# pH_meter.net
KiCad netlist of a schematic drawn in EAGLE
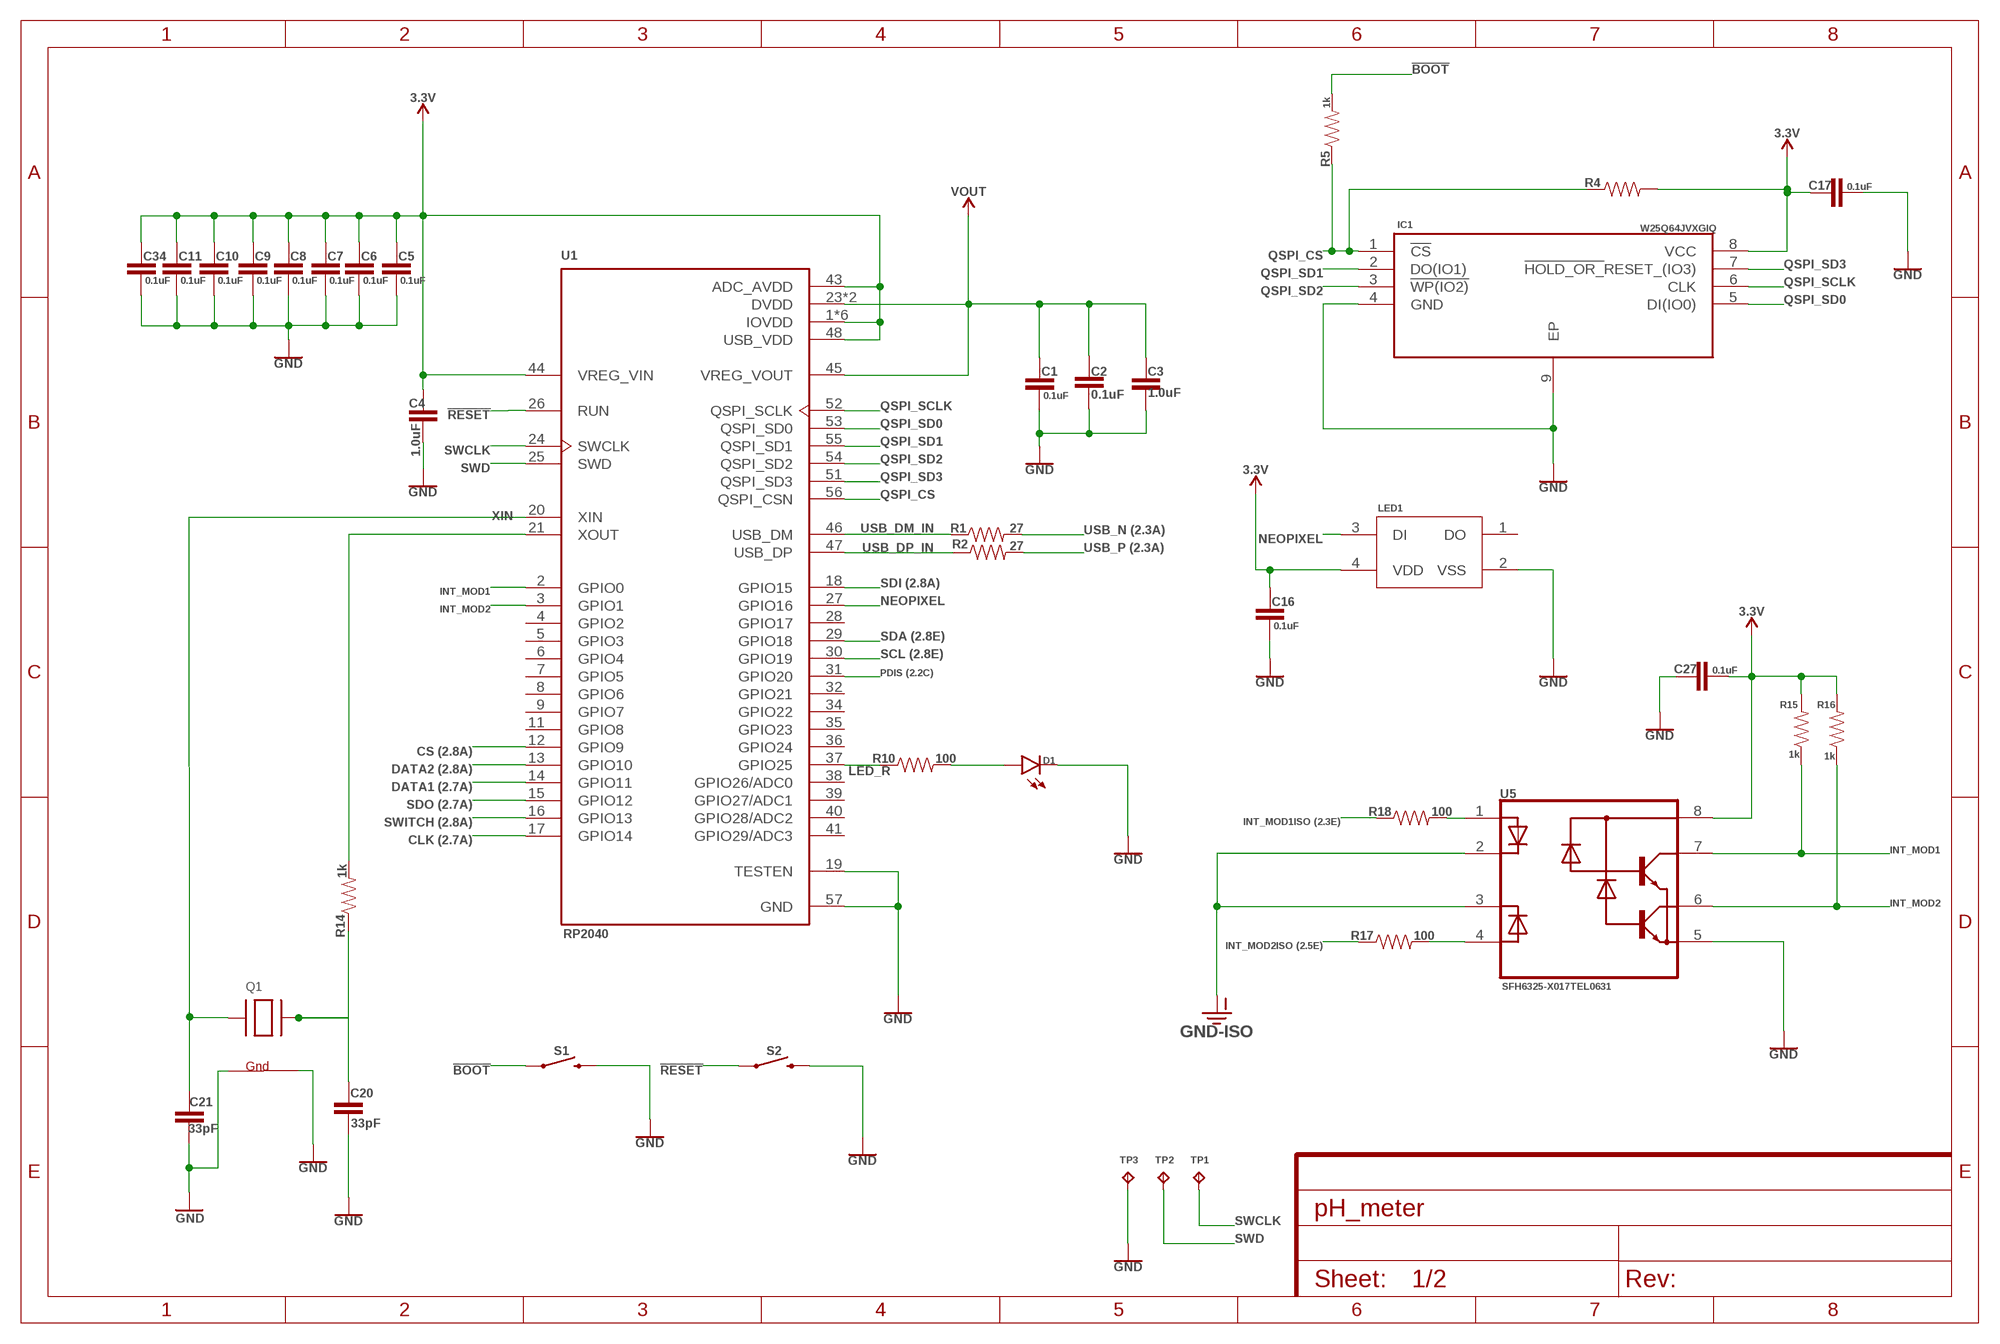
[diagram p0: schematic, sheet 1]
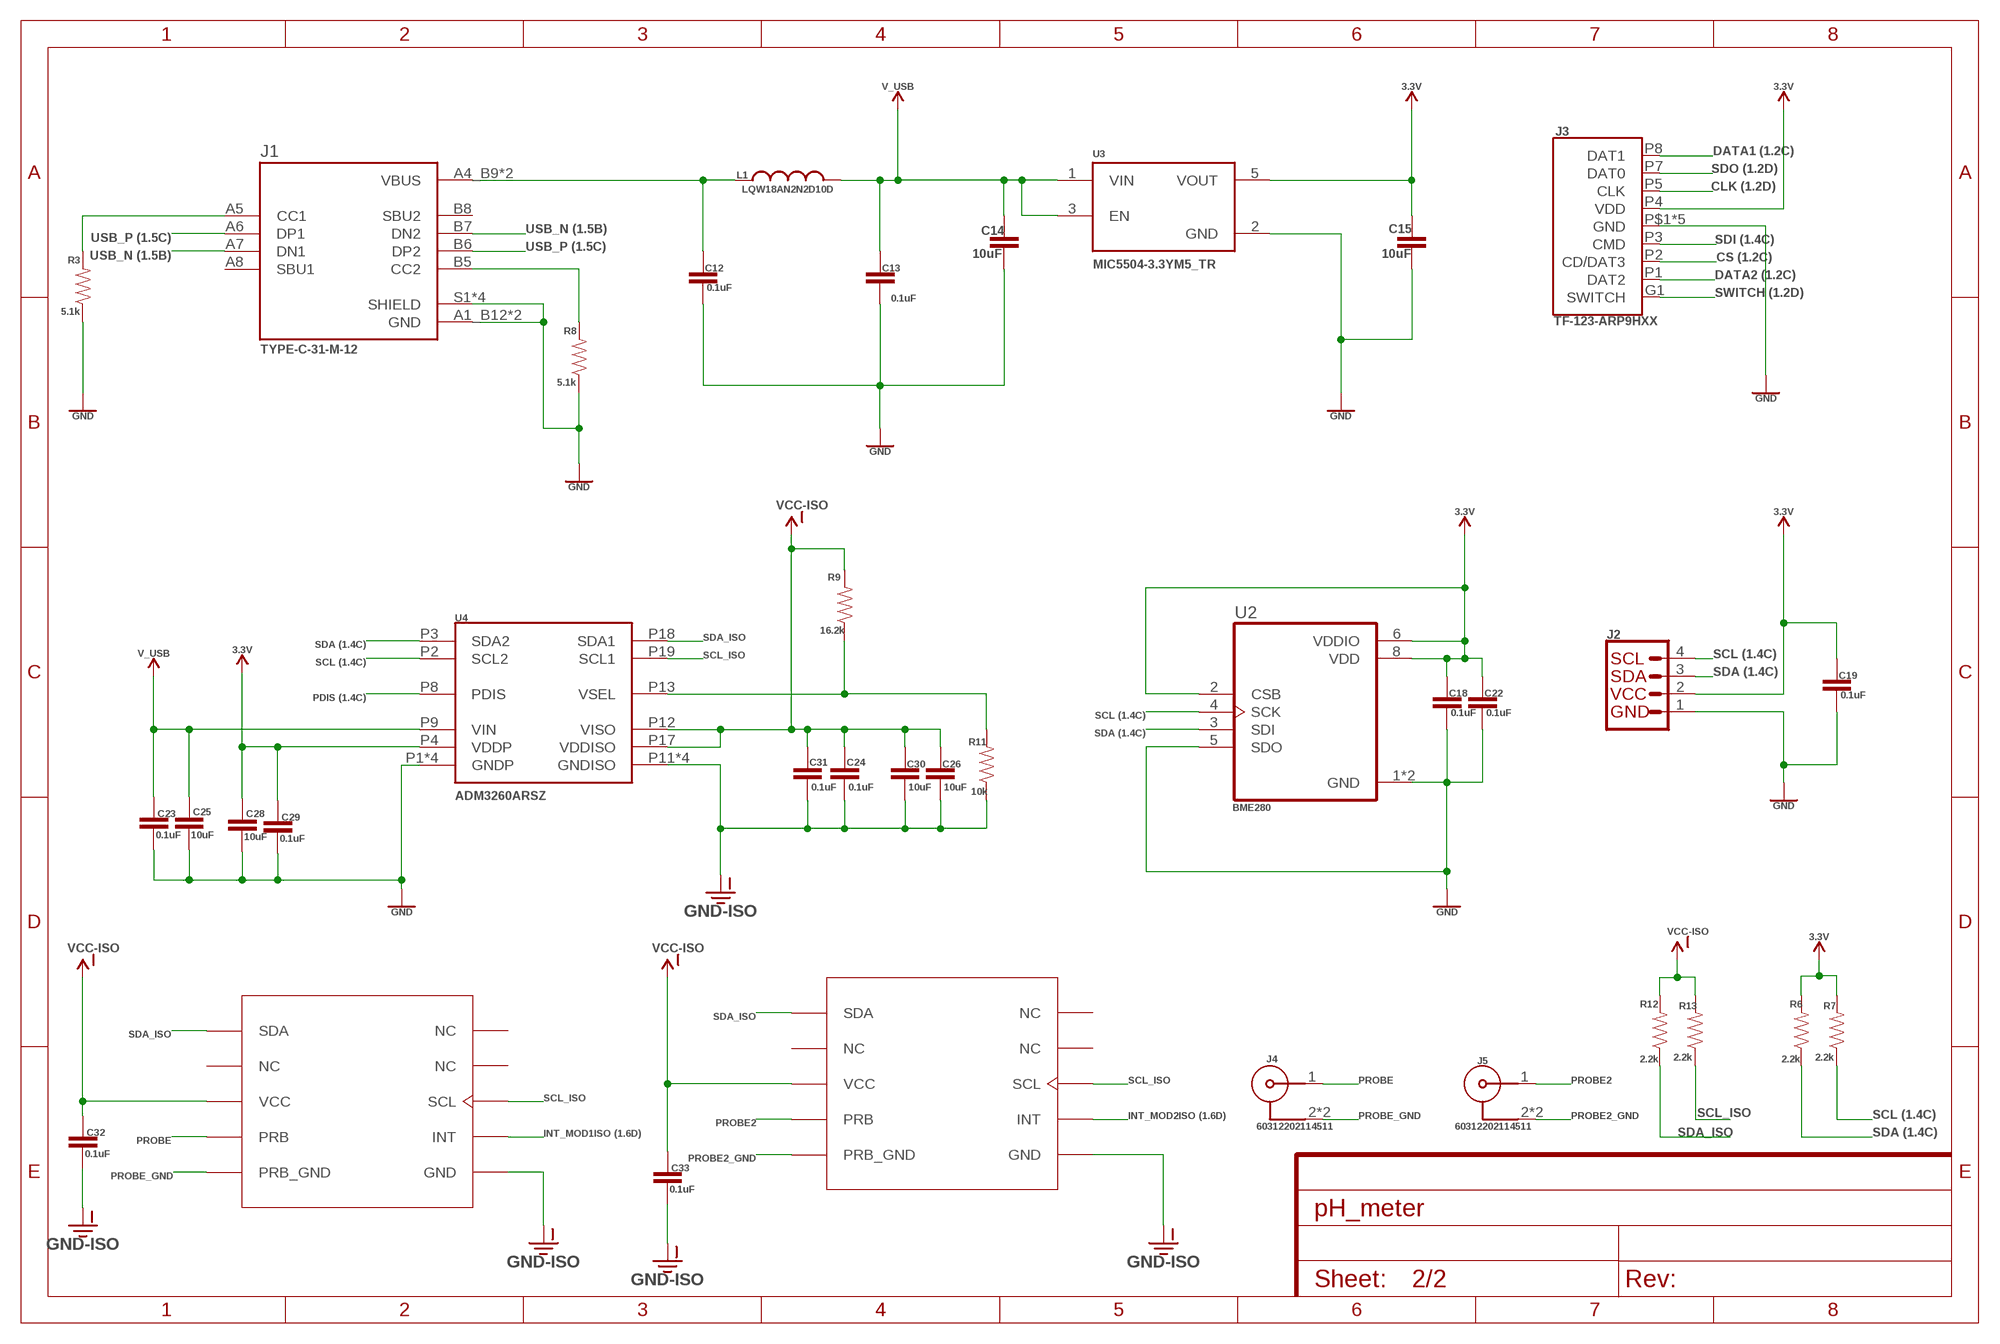
[diagram p1: schematic, sheet 2]

(export (version "E")
  (design (tool "Eeschema 10.0.6"))
  (components
    (comp (ref "C1")
      (value "0.1uF")
      (footprint "eagle-import:0603")
      (libsource (lib "eagle-import") (part "0.1UF-0603-25V-(+80/-20%)"))
    )
    (comp (ref "C2")
      (value "0.1uF")
      (footprint "eagle-import:0603")
      (libsource (lib "eagle-import") (part "0.1UF-0603-25V-(+80/-20%)"))
    )
    (comp (ref "C3")
      (value "1.0uF")
      (footprint "eagle-import:0603")
      (libsource (lib "eagle-import") (part "1.0UF-0603-16V-10%"))
    )
    (comp (ref "C4")
      (value "1.0uF")
      (footprint "eagle-import:0603")
      (libsource (lib "eagle-import") (part "1.0UF-0603-16V-10%"))
    )
    (comp (ref "C5")
      (value "0.1uF")
      (footprint "eagle-import:0603")
      (libsource (lib "eagle-import") (part "0.1UF-0603-25V-(+80/-20%)"))
    )
    (comp (ref "C6")
      (value "0.1uF")
      (footprint "eagle-import:0603")
      (libsource (lib "eagle-import") (part "0.1UF-0603-25V-(+80/-20%)"))
    )
    (comp (ref "C7")
      (value "0.1uF")
      (footprint "eagle-import:0603")
      (libsource (lib "eagle-import") (part "0.1UF-0603-25V-(+80/-20%)"))
    )
    (comp (ref "C8")
      (value "0.1uF")
      (footprint "eagle-import:0603")
      (libsource (lib "eagle-import") (part "0.1UF-0603-25V-(+80/-20%)"))
    )
    (comp (ref "C9")
      (value "0.1uF")
      (footprint "eagle-import:0603")
      (libsource (lib "eagle-import") (part "0.1UF-0603-25V-(+80/-20%)"))
    )
    (comp (ref "C10")
      (value "0.1uF")
      (footprint "eagle-import:0603")
      (libsource (lib "eagle-import") (part "0.1UF-0603-25V-(+80/-20%)"))
    )
    (comp (ref "C11")
      (value "0.1uF")
      (footprint "eagle-import:0603")
      (libsource (lib "eagle-import") (part "0.1UF-0603-25V-(+80/-20%)"))
    )
    (comp (ref "C16")
      (value "0.1uF")
      (footprint "eagle-import:0603")
      (libsource (lib "eagle-import") (part "0.1UF-0603-25V-(+80/-20%)"))
    )
    (comp (ref "C17")
      (value "0.1uF")
      (footprint "eagle-import:0603")
      (libsource (lib "eagle-import") (part "0.1UF-0603-25V-(+80/-20%)"))
    )
    (comp (ref "C20")
      (value "33pF")
      (footprint "eagle-import:0603")
      (libsource (lib "eagle-import") (part "33PF-0603-50V-5%"))
    )
    (comp (ref "C21")
      (value "33pF")
      (footprint "eagle-import:0603")
      (libsource (lib "eagle-import") (part "33PF-0603-50V-5%"))
    )
    (comp (ref "C27")
      (value "0.1uF")
      (footprint "eagle-import:0603")
      (libsource (lib "eagle-import") (part "0.1UF-0603-25V-(+80/-20%)"))
    )
    (comp (ref "C34")
      (value "0.1uF")
      (footprint "eagle-import:0603")
      (libsource (lib "eagle-import") (part "0.1UF-0603-25V-(+80/-20%)"))
    )
    (comp (ref "D1")
      (value "LED0603")
      (footprint "eagle-import:LED-0603")
      (libsource (lib "eagle-import") (part "LED0603"))
    )
    (comp (ref "IC1")
      (value "W25Q64JVXGIQ")
      (footprint "eagle-import:SON80P400X400X50-9N")
      (libsource (lib "eagle-import") (part "W25Q64JVXGIQ"))
    )
    (comp (ref "LED1")
      (value "WS2812B-2020")
      (footprint "eagle-import:WS2812B-2020")
      (fields (field (name "MF") "WorldSemi"))
      (libsource (lib "eagle-import") (part "WS2812B-2020"))
    )
    (comp (ref "Q1")
      (value "XTAL-4-3225")
      (footprint "eagle-import:NX3225")
      (libsource (lib "eagle-import") (part "XTAL-4-3225"))
    )
    (comp (ref "R1")
      (value "27")
      (footprint "eagle-import:0603")
      (libsource (lib "eagle-import") (part "27OHM-0603-1/10W-1%"))
    )
    (comp (ref "R2")
      (value "27")
      (footprint "eagle-import:0603")
      (libsource (lib "eagle-import") (part "27OHM-0603-1/10W-1%"))
    )
    (comp (ref "R4")
      (value "RESISTOR0603")
      (footprint "eagle-import:0603")
      (libsource (lib "eagle-import") (part "RESISTOR0603"))
    )
    (comp (ref "R5")
      (value "1k")
      (footprint "eagle-import:0603")
      (libsource (lib "eagle-import") (part "1KOHM-0603-1/10W-1%"))
    )
    (comp (ref "R10")
      (value "100")
      (footprint "eagle-import:0603")
      (libsource (lib "eagle-import") (part "100OHM-0603-1/10W-1%"))
    )
    (comp (ref "R14")
      (value "1k")
      (footprint "eagle-import:0603")
      (libsource (lib "eagle-import") (part "1KOHM-0603-1/10W-1%"))
    )
    (comp (ref "R15")
      (value "1k")
      (footprint "eagle-import:0603")
      (libsource (lib "eagle-import") (part "1KOHM-0603-1/10W-1%"))
    )
    (comp (ref "R16")
      (value "1k")
      (footprint "eagle-import:0603")
      (libsource (lib "eagle-import") (part "1KOHM-0603-1/10W-1%"))
    )
    (comp (ref "R17")
      (value "100")
      (footprint "eagle-import:0603")
      (libsource (lib "eagle-import") (part "100OHM-0603-1/10W-1%"))
    )
    (comp (ref "R18")
      (value "100")
      (footprint "eagle-import:0603")
      (libsource (lib "eagle-import") (part "100OHM-0603-1/10W-1%"))
    )
    (comp (ref "S1")
      (value "MOMENTARY-SWITCH-SPST-SMD-4.6X2.8MM")
      (footprint "eagle-import:TACTILE_SWITCH_SMD_4.6X2.8MM")
      (libsource (lib "eagle-import") (part "MOMENTARY-SWITCH-SPST-SMD-4.6X2.8MM"))
    )
    (comp (ref "S2")
      (value "MOMENTARY-SWITCH-SPST-SMD-4.6X2.8MM")
      (footprint "eagle-import:TACTILE_SWITCH_SMD_4.6X2.8MM")
      (libsource (lib "eagle-import") (part "MOMENTARY-SWITCH-SPST-SMD-4.6X2.8MM"))
    )
    (comp (ref "TP1")
      (value "TPB2,54")
      (footprint "eagle-import:B2,54")
      (libsource (lib "eagle-import") (part "TPB2,54"))
    )
    (comp (ref "TP2")
      (value "TPB2,54")
      (footprint "eagle-import:B2,54")
      (libsource (lib "eagle-import") (part "TPB2,54"))
    )
    (comp (ref "TP3")
      (value "TPB2,54")
      (footprint "eagle-import:B2,54")
      (libsource (lib "eagle-import") (part "TPB2,54"))
    )
    (comp (ref "U1")
      (value "RP2040")
      (footprint "eagle-import:QFN40P700X700X90-57N")
      (fields (field (name "MF") "Raspberry Pi"))
      (libsource (lib "eagle-import") (part "RP2040"))
    )
    (comp (ref "U5")
      (value "SFH6325-X017TEL0631")
      (footprint "eagle-import:SOIC127P599X175-8N")
      (libsource (lib "eagle-import") (part "SFH6325-X017TEL0631"))
    )
    (comp (ref "C12")
      (value "0.1uF")
      (footprint "eagle-import:0603")
      (libsource (lib "eagle-import") (part "0.1UF-0603-25V-(+80/-20%)"))
    )
    (comp (ref "C13")
      (value "0.1uF")
      (footprint "eagle-import:0603")
      (libsource (lib "eagle-import") (part "0.1UF-0603-25V-(+80/-20%)"))
    )
    (comp (ref "C14")
      (value "10uF")
      (footprint "eagle-import:0603")
      (libsource (lib "eagle-import") (part "10UF-0603-6.3V-20%"))
    )
    (comp (ref "C15")
      (value "10uF")
      (footprint "eagle-import:0603")
      (libsource (lib "eagle-import") (part "10UF-0603-6.3V-20%"))
    )
    (comp (ref "C18")
      (value "0.1uF")
      (footprint "eagle-import:0603")
      (libsource (lib "eagle-import") (part "0.1UF-0603-25V-5%"))
    )
    (comp (ref "C19")
      (value "0.1uF")
      (footprint "eagle-import:0603")
      (libsource (lib "eagle-import") (part "0.1UF-0603-25V-5%"))
    )
    (comp (ref "C22")
      (value "0.1uF")
      (footprint "eagle-import:0603")
      (libsource (lib "eagle-import") (part "0.1UF-0603-25V-5%"))
    )
    (comp (ref "C23")
      (value "0.1uF")
      (footprint "eagle-import:0603")
      (libsource (lib "eagle-import") (part "0.1UF-0603-25V-5%"))
    )
    (comp (ref "C24")
      (value "0.1uF")
      (footprint "eagle-import:0603")
      (libsource (lib "eagle-import") (part "0.1UF-0603-50V-10%-X7R-WE"))
    )
    (comp (ref "C25")
      (value "10uF")
      (footprint "eagle-import:0603")
      (libsource (lib "eagle-import") (part "10UF-0603-6.3V-20%"))
    )
    (comp (ref "C26")
      (value "10uF")
      (footprint "eagle-import:0603")
      (libsource (lib "eagle-import") (part "10UF-0603-6.3V-20%"))
    )
    (comp (ref "C28")
      (value "10uF")
      (footprint "eagle-import:0603")
      (libsource (lib "eagle-import") (part "10UF-0603-6.3V-20%"))
    )
    (comp (ref "C29")
      (value "0.1uF")
      (footprint "eagle-import:0603")
      (libsource (lib "eagle-import") (part "0.1UF-0603-25V-5%"))
    )
    (comp (ref "C30")
      (value "10uF")
      (footprint "eagle-import:0603")
      (libsource (lib "eagle-import") (part "10UF-0603-6.3V-20%"))
    )
    (comp (ref "C31")
      (value "0.1uF")
      (footprint "eagle-import:0603")
      (libsource (lib "eagle-import") (part "0.1UF-0603-50V-10%-X7R-WE"))
    )
    (comp (ref "C32")
      (value "0.1uF")
      (footprint "eagle-import:0603")
      (libsource (lib "eagle-import") (part "0.1UF-0603-25V-5%"))
    )
    (comp (ref "C33")
      (value "0.1uF")
      (footprint "eagle-import:0603")
      (libsource (lib "eagle-import") (part "0.1UF-0603-25V-5%"))
    )
    (comp (ref "J1")
      (value "TYPE-C-31-M-12")
      (footprint "eagle-import:HRO_TYPE-C-31-M-12")
      (fields (field (name "MF") "HRO Electronics Co., Ltd."))
      (libsource (lib "eagle-import") (part "TYPE-C-31-M-12"))
    )
    (comp (ref "J2")
      (value "QWIIC_CONNECTORJS-1MM")
      (footprint "eagle-import:1X04_1MM_RA")
      (libsource (lib "eagle-import") (part "QWIIC_CONNECTORJS-1MM"))
    )
    (comp (ref "J3")
      (value "TF-123-ARP9HXX")
      (footprint "eagle-import:MICROSDCARD")
      (libsource (lib "eagle-import") (part "TF-123-ARP9HXX"))
    )
    (comp (ref "J4")
      (value "60312202114511")
      (footprint "eagle-import:60312202114511")
      (fields (field (name "MF") "Wurth Electronics"))
      (libsource (lib "eagle-import") (part "60312202114511"))
    )
    (comp (ref "J5")
      (value "60312202114511")
      (footprint "eagle-import:60312202114511")
      (fields (field (name "MF") "Wurth Electronics"))
      (libsource (lib "eagle-import") (part "60312202114511"))
    )
    (comp (ref "L1")
      (value "LQW18AN2N2D10D")
      (footprint "eagle-import:INDC1608X100N")
      (fields (field (name "MF") "Murata"))
      (libsource (lib "eagle-import") (part "LQW18AN2N2D10D"))
    )
    (comp (ref "R3")
      (value "5.1k")
      (footprint "eagle-import:0603")
      (libsource (lib "eagle-import") (part "5.1KOHM5.1KOHM-0603-1/10W-1%"))
    )
    (comp (ref "R6")
      (value "2.2k")
      (footprint "eagle-import:0603")
      (libsource (lib "eagle-import") (part "2.2KOHM-0603-1/10W-1%"))
    )
    (comp (ref "R7")
      (value "2.2k")
      (footprint "eagle-import:0603")
      (libsource (lib "eagle-import") (part "2.2KOHM-0603-1/10W-1%"))
    )
    (comp (ref "R8")
      (value "5.1k")
      (footprint "eagle-import:0603")
      (libsource (lib "eagle-import") (part "5.1KOHM5.1KOHM-0603-1/10W-1%"))
    )
    (comp (ref "R9")
      (value "16.2k")
      (footprint "eagle-import:0603")
      (libsource (lib "eagle-import") (part "16.2KOHM-0603-1/10W-1%"))
    )
    (comp (ref "R11")
      (value "10k")
      (footprint "eagle-import:0603")
      (libsource (lib "eagle-import") (part "10KOHM-0603-1/10W-1%"))
    )
    (comp (ref "R12")
      (value "2.2k")
      (footprint "eagle-import:0603")
      (libsource (lib "eagle-import") (part "2.2KOHM-0603-1/10W-1%"))
    )
    (comp (ref "R13")
      (value "2.2k")
      (footprint "eagle-import:0603")
      (libsource (lib "eagle-import") (part "2.2KOHM-0603-1/10W-1%"))
    )
    (comp (ref "U$1")
      (value "PH-OEM")
      (footprint "eagle-import:PH_SENSOR")
      (libsource (lib "eagle-import") (part "PH-OEM"))
    )
    (comp (ref "U$2")
      (value "PH-OEM")
      (footprint "eagle-import:PH_SENSOR")
      (libsource (lib "eagle-import") (part "PH-OEM"))
    )
    (comp (ref "U2")
      (value "BME280")
      (footprint "eagle-import:PSON65P250X250X100-8N")
      (fields (field (name "MF") "Bosch"))
      (libsource (lib "eagle-import") (part "BME280"))
    )
    (comp (ref "U3")
      (value "MIC5504-3.3YM5_TR")
      (footprint "eagle-import:SOT95P280X145-5N")
      (fields (field (name "MF") "Microchip") (field (name "MP") "MIC5504-3.3YM5 TR"))
      (libsource (lib "eagle-import") (part "MIC5504-3.3YM5_TR"))
    )
    (comp (ref "U4")
      (value "ADM3260ARSZ")
      (footprint "eagle-import:SSOP20")
      (fields (field (name "MF") "Analog Devices"))
      (libsource (lib "eagle-import") (part "ADM3260ARSZ"))
    )
  )
  (nets
    (net (code "1") (name "3.3V") (class "Default")
      (node (ref "C10") (pin "1") (pinfunction "1_1") (pintype "passive"))
      (node (ref "C11") (pin "1") (pinfunction "1_1") (pintype "passive"))
      (node (ref "C15") (pin "2") (pinfunction "2_2") (pintype "passive"))
      (node (ref "C16") (pin "1") (pinfunction "1_1") (pintype "passive"))
      (node (ref "C17") (pin "1") (pinfunction "1_1") (pintype "passive"))
      (node (ref "C18") (pin "1") (pinfunction "1_1") (pintype "passive"))
      (node (ref "C19") (pin "1") (pinfunction "1_1") (pintype "passive"))
      (node (ref "C22") (pin "1") (pinfunction "1_1") (pintype "passive"))
      (node (ref "C27") (pin "2") (pinfunction "2_2") (pintype "passive"))
      (node (ref "C28") (pin "1") (pinfunction "1_1") (pintype "passive"))
      (node (ref "C29") (pin "1") (pinfunction "1_1") (pintype "passive"))
      (node (ref "C34") (pin "1") (pinfunction "1_1") (pintype "passive"))
      (node (ref "C4") (pin "1") (pinfunction "1_1") (pintype "passive"))
      (node (ref "C5") (pin "1") (pinfunction "1_1") (pintype "passive"))
      (node (ref "C6") (pin "1") (pinfunction "1_1") (pintype "passive"))
      (node (ref "C7") (pin "1") (pinfunction "1_1") (pintype "passive"))
      (node (ref "C8") (pin "1") (pinfunction "1_1") (pintype "passive"))
      (node (ref "C9") (pin "1") (pinfunction "1_1") (pintype "passive"))
      (node (ref "IC1") (pin "8") (pinfunction "VCC_8") (pintype "bidirectional"))
      (node (ref "J2") (pin "2") (pinfunction "2_2") (pintype "power_in"))
      (node (ref "J3") (pin "P4") (pinfunction "VDD_P4") (pintype "power_in"))
      (node (ref "LED1") (pin "4") (pinfunction "VDD_4") (pintype "bidirectional"))
      (node (ref "R15") (pin "2") (pinfunction "2_2") (pintype "passive"))
      (node (ref "R16") (pin "2") (pinfunction "2_2") (pintype "passive"))
      (node (ref "R4") (pin "2") (pinfunction "2_2") (pintype "passive"))
      (node (ref "R6") (pin "2") (pinfunction "2_2") (pintype "passive"))
      (node (ref "R7") (pin "2") (pinfunction "2_2") (pintype "passive"))
      (node (ref "U1") (pin "1") (pinfunction "IOVDD_1") (pintype "power_in"))
      (node (ref "U1") (pin "10") (pinfunction "IOVDD_10") (pintype "power_in"))
      (node (ref "U1") (pin "22") (pinfunction "IOVDD_22") (pintype "power_in"))
      (node (ref "U1") (pin "33") (pinfunction "IOVDD_33") (pintype "power_in"))
      (node (ref "U1") (pin "42") (pinfunction "IOVDD_42") (pintype "power_in"))
      (node (ref "U1") (pin "43") (pinfunction "ADC_AVDD_43") (pintype "power_in"))
      (node (ref "U1") (pin "44") (pinfunction "VREG_VIN_44") (pintype "input"))
      (node (ref "U1") (pin "48") (pinfunction "USB_VDD_48") (pintype "power_in"))
      (node (ref "U1") (pin "49") (pinfunction "IOVDD_49") (pintype "power_in"))
      (node (ref "U2") (pin "2") (pinfunction "CSB_2") (pintype "input"))
      (node (ref "U2") (pin "6") (pinfunction "VDDIO_6") (pintype "power_in"))
      (node (ref "U2") (pin "8") (pinfunction "VDD_8") (pintype "power_in"))
      (node (ref "U3") (pin "5") (pinfunction "VOUT_5") (pintype "output"))
      (node (ref "U4") (pin "P4") (pinfunction "VDDP_P4") (pintype "bidirectional"))
      (node (ref "U5") (pin "8") (pinfunction "C(VCC)_8") (pintype "passive"))
    )
    (net (code "2") (name "CLK") (class "Default")
      (node (ref "J3") (pin "P5") (pinfunction "CLK_P5") (pintype "bidirectional"))
      (node (ref "U1") (pin "17") (pinfunction "GPIO14_17") (pintype "bidirectional"))
    )
    (net (code "3") (name "CS") (class "Default")
      (node (ref "J3") (pin "P2") (pinfunction "CD/DAT3_P2") (pintype "bidirectional"))
      (node (ref "U1") (pin "12") (pinfunction "GPIO9_12") (pintype "bidirectional"))
    )
    (net (code "4") (name "DATA1") (class "Default")
      (node (ref "J3") (pin "P8") (pinfunction "DAT1_P8") (pintype "bidirectional"))
      (node (ref "U1") (pin "14") (pinfunction "GPIO11_14") (pintype "bidirectional"))
    )
    (net (code "5") (name "DATA2") (class "Default")
      (node (ref "J3") (pin "P1") (pinfunction "DAT2_P1") (pintype "bidirectional"))
      (node (ref "U1") (pin "13") (pinfunction "GPIO10_13") (pintype "bidirectional"))
    )
    (net (code "6") (name "GND") (class "Default")
      (node (ref "C1") (pin "2") (pinfunction "2_2") (pintype "passive"))
      (node (ref "C10") (pin "2") (pinfunction "2_2") (pintype "passive"))
      (node (ref "C11") (pin "2") (pinfunction "2_2") (pintype "passive"))
      (node (ref "C12") (pin "2") (pinfunction "2_2") (pintype "passive"))
      (node (ref "C13") (pin "2") (pinfunction "2_2") (pintype "passive"))
      (node (ref "C14") (pin "1") (pinfunction "1_1") (pintype "passive"))
      (node (ref "C15") (pin "1") (pinfunction "1_1") (pintype "passive"))
      (node (ref "C16") (pin "2") (pinfunction "2_2") (pintype "passive"))
      (node (ref "C17") (pin "2") (pinfunction "2_2") (pintype "passive"))
      (node (ref "C18") (pin "2") (pinfunction "2_2") (pintype "passive"))
      (node (ref "C19") (pin "2") (pinfunction "2_2") (pintype "passive"))
      (node (ref "C2") (pin "2") (pinfunction "2_2") (pintype "passive"))
      (node (ref "C20") (pin "1") (pinfunction "1_1") (pintype "passive"))
      (node (ref "C21") (pin "1") (pinfunction "1_1") (pintype "passive"))
      (node (ref "C22") (pin "2") (pinfunction "2_2") (pintype "passive"))
      (node (ref "C23") (pin "2") (pinfunction "2_2") (pintype "passive"))
      (node (ref "C25") (pin "2") (pinfunction "2_2") (pintype "passive"))
      (node (ref "C27") (pin "1") (pinfunction "1_1") (pintype "passive"))
      (node (ref "C28") (pin "2") (pinfunction "2_2") (pintype "passive"))
      (node (ref "C29") (pin "2") (pinfunction "2_2") (pintype "passive"))
      (node (ref "C3") (pin "2") (pinfunction "2_2") (pintype "passive"))
      (node (ref "C34") (pin "2") (pinfunction "2_2") (pintype "passive"))
      (node (ref "C4") (pin "2") (pinfunction "2_2") (pintype "passive"))
      (node (ref "C5") (pin "2") (pinfunction "2_2") (pintype "passive"))
      (node (ref "C6") (pin "2") (pinfunction "2_2") (pintype "passive"))
      (node (ref "C7") (pin "2") (pinfunction "2_2") (pintype "passive"))
      (node (ref "C8") (pin "2") (pinfunction "2_2") (pintype "passive"))
      (node (ref "C9") (pin "2") (pinfunction "2_2") (pintype "passive"))
      (node (ref "D1") (pin "C") (pinfunction "C_C") (pintype "passive"))
      (node (ref "IC1") (pin "4") (pinfunction "GND_4") (pintype "bidirectional"))
      (node (ref "IC1") (pin "9") (pinfunction "EP_9") (pintype "bidirectional"))
      (node (ref "J1") (pin "A1_B12") (pinfunction "GND_A1_B12") (pintype "power_in"))
      (node (ref "J1") (pin "B1_A12") (pinfunction "GND_B1_A12") (pintype "power_in"))
      (node (ref "J1") (pin "S1") (pinfunction "SHIELD_S1") (pintype "passive"))
      (node (ref "J1") (pin "S2") (pinfunction "SHIELD_S2") (pintype "passive"))
      (node (ref "J1") (pin "S3") (pinfunction "SHIELD_S3") (pintype "passive"))
      (node (ref "J1") (pin "S4") (pinfunction "SHIELD_S4") (pintype "passive"))
      (node (ref "J2") (pin "1") (pinfunction "1_1") (pintype "power_in"))
      (node (ref "J3") (pin "P$1") (pinfunction "GND_P$1") (pintype "power_in"))
      (node (ref "J3") (pin "P$2") (pinfunction "GND_P$2") (pintype "power_in"))
      (node (ref "J3") (pin "P$3") (pinfunction "GND_P$3") (pintype "power_in"))
      (node (ref "J3") (pin "P$4") (pinfunction "GND_P$4") (pintype "power_in"))
      (node (ref "J3") (pin "P6") (pinfunction "GND_P6") (pintype "power_in"))
      (node (ref "LED1") (pin "2") (pinfunction "VSS_2") (pintype "bidirectional"))
      (node (ref "Q1") (pin "2") (pinfunction "G2_2") (pintype "power_in"))
      (node (ref "Q1") (pin "4") (pinfunction "G1_4") (pintype "power_in"))
      (node (ref "R3") (pin "1") (pinfunction "1_1") (pintype "passive"))
      (node (ref "R8") (pin "1") (pinfunction "1_1") (pintype "passive"))
      (node (ref "S1") (pin "3") (pinfunction "2_3") (pintype "passive"))
      (node (ref "S1") (pin "4") (pinfunction "2_4") (pintype "passive"))
      (node (ref "S2") (pin "3") (pinfunction "2_3") (pintype "passive"))
      (node (ref "S2") (pin "4") (pinfunction "2_4") (pintype "passive"))
      (node (ref "TP3") (pin "TP") (pinfunction "TP_TP") (pintype "input"))
      (node (ref "U1") (pin "19") (pinfunction "TESTEN_19") (pintype "passive"))
      (node (ref "U1") (pin "57") (pinfunction "GND_57") (pintype "power_in"))
      (node (ref "U2") (pin "1") (pinfunction "GND_1") (pintype "power_in"))
      (node (ref "U2") (pin "5") (pinfunction "SDO_5") (pintype "bidirectional"))
      (node (ref "U2") (pin "7") (pinfunction "GND_7") (pintype "power_in"))
      (node (ref "U3") (pin "2") (pinfunction "GND_2") (pintype "power_in"))
      (node (ref "U4") (pin "P1") (pinfunction "GNDP_P1") (pintype "bidirectional"))
      (node (ref "U4") (pin "P10") (pinfunction "GNDP_P10") (pintype "bidirectional"))
      (node (ref "U4") (pin "P5") (pinfunction "GNDP_P5") (pintype "bidirectional"))
      (node (ref "U4") (pin "P7") (pinfunction "GNDP_P7") (pintype "bidirectional"))
      (node (ref "U5") (pin "5") (pinfunction "E(GND)_5") (pintype "passive"))
    )
    (net (code "7") (name "GND-ISO") (class "Default")
      (node (ref "C24") (pin "2") (pinfunction "2_2") (pintype "passive"))
      (node (ref "C26") (pin "2") (pinfunction "2_2") (pintype "passive"))
      (node (ref "C30") (pin "2") (pinfunction "2_2") (pintype "passive"))
      (node (ref "C31") (pin "2") (pinfunction "2_2") (pintype "passive"))
      (node (ref "C32") (pin "2") (pinfunction "2_2") (pintype "passive"))
      (node (ref "C33") (pin "2") (pinfunction "2_2") (pintype "passive"))
      (node (ref "R11") (pin "1") (pinfunction "1_1") (pintype "passive"))
      (node (ref "U$1") (pin "P$6") (pinfunction "GND_P$6") (pintype "power_in"))
      (node (ref "U$2") (pin "P$6") (pinfunction "GND_P$6") (pintype "power_in"))
      (node (ref "U4") (pin "P11") (pinfunction "GNDISO_P11") (pintype "bidirectional"))
      (node (ref "U4") (pin "P14") (pinfunction "GNDISO_P14") (pintype "bidirectional"))
      (node (ref "U4") (pin "P16") (pinfunction "GNDISO_P16") (pintype "bidirectional"))
      (node (ref "U4") (pin "P20") (pinfunction "GNDISO_P20") (pintype "bidirectional"))
      (node (ref "U5") (pin "2") (pinfunction "C1_2") (pintype "passive"))
      (node (ref "U5") (pin "3") (pinfunction "C2_3") (pintype "passive"))
    )
    (net (code "8") (name "INT_MOD1") (class "Default")
      (node (ref "R15") (pin "1") (pinfunction "1_1") (pintype "passive"))
      (node (ref "U1") (pin "2") (pinfunction "GPIO0_2") (pintype "bidirectional"))
      (node (ref "U5") (pin "7") (pinfunction "C1(VO1)_7") (pintype "passive"))
    )
    (net (code "9") (name "INT_MOD1ISO") (class "Default")
      (node (ref "R18") (pin "1") (pinfunction "1_1") (pintype "passive"))
      (node (ref "U$2") (pin "P$7") (pinfunction "INT_P$7") (pintype "bidirectional"))
    )
    (net (code "10") (name "INT_MOD2") (class "Default")
      (node (ref "R16") (pin "1") (pinfunction "1_1") (pintype "passive"))
      (node (ref "U1") (pin "3") (pinfunction "GPIO1_3") (pintype "bidirectional"))
      (node (ref "U5") (pin "6") (pinfunction "C2(VO2)_6") (pintype "passive"))
    )
    (net (code "11") (name "INT_MOD2ISO") (class "Default")
      (node (ref "R17") (pin "1") (pinfunction "1_1") (pintype "passive"))
      (node (ref "U$1") (pin "P$7") (pinfunction "INT_P$7") (pintype "bidirectional"))
    )
    (net (code "12") (name "LED_R") (class "Default")
      (node (ref "R10") (pin "1") (pinfunction "1_1") (pintype "passive"))
      (node (ref "U1") (pin "37") (pinfunction "GPIO25_37") (pintype "bidirectional"))
    )
    (net (code "13") (name "NEOPIXEL") (class "Default")
      (node (ref "LED1") (pin "3") (pinfunction "DI_3") (pintype "bidirectional"))
      (node (ref "U1") (pin "27") (pinfunction "GPIO16_27") (pintype "bidirectional"))
    )
    (net (code "14") (name "Net-(C12-Pad1)") (class "Default")
      (node (ref "C12") (pin "1") (pinfunction "1_1") (pintype "passive"))
      (node (ref "J1") (pin "A4_B9") (pinfunction "VBUS_A4_B9") (pintype "power_in"))
      (node (ref "J1") (pin "B4_A9") (pinfunction "VBUS_B4_A9") (pintype "power_in"))
      (node (ref "L1") (pin "1") (pinfunction "1_1") (pintype "passive"))
    )
    (net (code "15") (name "Net-(D1-PadA)") (class "Default")
      (node (ref "D1") (pin "A") (pinfunction "A_A") (pintype "passive"))
      (node (ref "R10") (pin "2") (pinfunction "2_2") (pintype "passive"))
    )
    (net (code "16") (name "Net-(J1-CC1)") (class "Default")
      (node (ref "J1") (pin "A5") (pinfunction "CC1_A5") (pintype "bidirectional"))
      (node (ref "R3") (pin "2") (pinfunction "2_2") (pintype "passive"))
    )
    (net (code "17") (name "Net-(J1-CC2)") (class "Default")
      (node (ref "J1") (pin "B5") (pinfunction "CC2_B5") (pintype "bidirectional"))
      (node (ref "R8") (pin "2") (pinfunction "2_2") (pintype "passive"))
    )
    (net (code "18") (name "Net-(Q1-X2)") (class "Default")
      (node (ref "C20") (pin "2") (pinfunction "2_2") (pintype "passive"))
      (node (ref "Q1") (pin "3") (pinfunction "X2_3") (pintype "bidirectional"))
      (node (ref "R14") (pin "1") (pinfunction "1_1") (pintype "passive"))
    )
    (net (code "19") (name "Net-(U1-XOUT)") (class "Default")
      (node (ref "R14") (pin "2") (pinfunction "2_2") (pintype "passive"))
      (node (ref "U1") (pin "21") (pinfunction "XOUT_21") (pintype "output"))
    )
    (net (code "20") (name "Net-(U4-VSEL)") (class "Default")
      (node (ref "R11") (pin "2") (pinfunction "2_2") (pintype "passive"))
      (node (ref "R9") (pin "1") (pinfunction "1_1") (pintype "passive"))
      (node (ref "U4") (pin "P13") (pinfunction "VSEL_P13") (pintype "bidirectional"))
    )
    (net (code "21") (name "Net-(U5-A1)") (class "Default")
      (node (ref "R18") (pin "2") (pinfunction "2_2") (pintype "passive"))
      (node (ref "U5") (pin "1") (pinfunction "A1_1") (pintype "passive"))
    )
    (net (code "22") (name "Net-(U5-A2)") (class "Default")
      (node (ref "R17") (pin "2") (pinfunction "2_2") (pintype "passive"))
      (node (ref "U5") (pin "4") (pinfunction "A2_4") (pintype "passive"))
    )
    (net (code "23") (name "PDIS") (class "Default")
      (node (ref "U1") (pin "31") (pinfunction "GPIO20_31") (pintype "bidirectional"))
      (node (ref "U4") (pin "P8") (pinfunction "PDIS_P8") (pintype "bidirectional"))
    )
    (net (code "24") (name "PROBE") (class "Default")
      (node (ref "J4") (pin "1") (pinfunction "1_1") (pintype "passive"))
      (node (ref "U$2") (pin "P$4") (pinfunction "PRB_P$4") (pintype "bidirectional"))
    )
    (net (code "25") (name "PROBE2") (class "Default")
      (node (ref "J5") (pin "1") (pinfunction "1_1") (pintype "passive"))
      (node (ref "U$1") (pin "P$4") (pinfunction "PRB_P$4") (pintype "bidirectional"))
    )
    (net (code "26") (name "PROBE2_GND") (class "Default")
      (node (ref "J5") (pin "2") (pinfunction "2_2") (pintype "passive"))
      (node (ref "J5") (pin "3") (pinfunction "2_3") (pintype "passive"))
      (node (ref "U$1") (pin "P$5") (pinfunction "PRB_GND_P$5") (pintype "bidirectional"))
    )
    (net (code "27") (name "PROBE_GND") (class "Default")
      (node (ref "J4") (pin "2") (pinfunction "2_2") (pintype "passive"))
      (node (ref "J4") (pin "3") (pinfunction "2_3") (pintype "passive"))
      (node (ref "U$2") (pin "P$5") (pinfunction "PRB_GND_P$5") (pintype "bidirectional"))
    )
    (net (code "28") (name "QSPI_CS") (class "Default")
      (node (ref "IC1") (pin "1") (pinfunction "~{CS}_1") (pintype "bidirectional"))
      (node (ref "R4") (pin "1") (pinfunction "1_1") (pintype "passive"))
      (node (ref "R5") (pin "1") (pinfunction "1_1") (pintype "passive"))
      (node (ref "U1") (pin "56") (pinfunction "QSPI_CSN_56") (pintype "bidirectional"))
    )
    (net (code "29") (name "QSPI_SCLK") (class "Default")
      (node (ref "IC1") (pin "6") (pinfunction "CLK_6") (pintype "bidirectional"))
      (node (ref "U1") (pin "52") (pinfunction "QSPI_SCLK_52") (pintype "bidirectional"))
    )
    (net (code "30") (name "QSPI_SD0") (class "Default")
      (node (ref "IC1") (pin "5") (pinfunction "DI(IO0)_5") (pintype "bidirectional"))
      (node (ref "U1") (pin "53") (pinfunction "QSPI_SD0_53") (pintype "bidirectional"))
    )
    (net (code "31") (name "QSPI_SD1") (class "Default")
      (node (ref "IC1") (pin "2") (pinfunction "DO(IO1)_2") (pintype "bidirectional"))
      (node (ref "U1") (pin "55") (pinfunction "QSPI_SD1_55") (pintype "bidirectional"))
    )
    (net (code "32") (name "QSPI_SD2") (class "Default")
      (node (ref "IC1") (pin "3") (pinfunction "~{WP(IO2})_3") (pintype "bidirectional"))
      (node (ref "U1") (pin "54") (pinfunction "QSPI_SD2_54") (pintype "bidirectional"))
    )
    (net (code "33") (name "QSPI_SD3") (class "Default")
      (node (ref "IC1") (pin "7") (pinfunction "~{HOLD_OR_}RESET_(IO3)_7") (pintype "bidirectional"))
      (node (ref "U1") (pin "51") (pinfunction "QSPI_SD3_51") (pintype "bidirectional"))
    )
    (net (code "34") (name "SCL") (class "Default")
      (node (ref "J2") (pin "4") (pinfunction "4_4") (pintype "passive"))
      (node (ref "R7") (pin "1") (pinfunction "1_1") (pintype "passive"))
      (node (ref "U1") (pin "30") (pinfunction "GPIO19_30") (pintype "bidirectional"))
      (node (ref "U2") (pin "4") (pinfunction "SCK_4") (pintype "input"))
      (node (ref "U4") (pin "P2") (pinfunction "SCL2_P2") (pintype "bidirectional"))
    )
    (net (code "35") (name "SCL_ISO") (class "Default")
      (node (ref "R13") (pin "1") (pinfunction "1_1") (pintype "passive"))
      (node (ref "U$1") (pin "P$8") (pinfunction "SCL_P$8") (pintype "bidirectional"))
      (node (ref "U$2") (pin "P$8") (pinfunction "SCL_P$8") (pintype "bidirectional"))
      (node (ref "U4") (pin "P19") (pinfunction "SCL1_P19") (pintype "bidirectional"))
    )
    (net (code "36") (name "SDA") (class "Default")
      (node (ref "J2") (pin "3") (pinfunction "3_3") (pintype "passive"))
      (node (ref "R6") (pin "1") (pinfunction "1_1") (pintype "passive"))
      (node (ref "U1") (pin "29") (pinfunction "GPIO18_29") (pintype "bidirectional"))
      (node (ref "U2") (pin "3") (pinfunction "SDI_3") (pintype "bidirectional"))
      (node (ref "U4") (pin "P3") (pinfunction "SDA2_P3") (pintype "bidirectional"))
    )
    (net (code "37") (name "SDA_ISO") (class "Default")
      (node (ref "R12") (pin "1") (pinfunction "1_1") (pintype "passive"))
      (node (ref "U$1") (pin "P$1") (pinfunction "SDA_P$1") (pintype "bidirectional"))
      (node (ref "U$2") (pin "P$1") (pinfunction "SDA_P$1") (pintype "bidirectional"))
      (node (ref "U4") (pin "P18") (pinfunction "SDA1_P18") (pintype "bidirectional"))
    )
    (net (code "38") (name "SDI") (class "Default")
      (node (ref "J3") (pin "P3") (pinfunction "CMD_P3") (pintype "bidirectional"))
      (node (ref "U1") (pin "18") (pinfunction "GPIO15_18") (pintype "bidirectional"))
    )
    (net (code "39") (name "SDO") (class "Default")
      (node (ref "J3") (pin "P7") (pinfunction "DAT0_P7") (pintype "bidirectional"))
      (node (ref "U1") (pin "15") (pinfunction "GPIO12_15") (pintype "bidirectional"))
    )
    (net (code "40") (name "SWCLK") (class "Default")
      (node (ref "TP1") (pin "TP") (pinfunction "TP_TP") (pintype "input"))
      (node (ref "U1") (pin "24") (pinfunction "SWCLK_24") (pintype "input"))
    )
    (net (code "41") (name "SWD") (class "Default")
      (node (ref "TP2") (pin "TP") (pinfunction "TP_TP") (pintype "input"))
      (node (ref "U1") (pin "25") (pinfunction "SWD_25") (pintype "bidirectional"))
    )
    (net (code "42") (name "SWITCH") (class "Default")
      (node (ref "J3") (pin "G1") (pinfunction "SWITCH_G1") (pintype "bidirectional"))
      (node (ref "U1") (pin "16") (pinfunction "GPIO13_16") (pintype "bidirectional"))
    )
    (net (code "43") (name "USB_DM_IN") (class "Default")
      (node (ref "R1") (pin "1") (pinfunction "1_1") (pintype "passive"))
      (node (ref "U1") (pin "46") (pinfunction "USB_DM_46") (pintype "bidirectional"))
    )
    (net (code "44") (name "USB_DP_IN") (class "Default")
      (node (ref "R2") (pin "1") (pinfunction "1_1") (pintype "passive"))
      (node (ref "U1") (pin "47") (pinfunction "USB_DP_47") (pintype "bidirectional"))
    )
    (net (code "45") (name "USB_N") (class "Default")
      (node (ref "J1") (pin "A7") (pinfunction "DN1_A7") (pintype "bidirectional"))
      (node (ref "J1") (pin "B7") (pinfunction "DN2_B7") (pintype "bidirectional"))
      (node (ref "R1") (pin "2") (pinfunction "2_2") (pintype "passive"))
    )
    (net (code "46") (name "USB_P") (class "Default")
      (node (ref "J1") (pin "A6") (pinfunction "DP1_A6") (pintype "bidirectional"))
      (node (ref "J1") (pin "B6") (pinfunction "DP2_B6") (pintype "bidirectional"))
      (node (ref "R2") (pin "2") (pinfunction "2_2") (pintype "passive"))
    )
    (net (code "47") (name "VCC-ISO") (class "Default")
      (node (ref "C24") (pin "1") (pinfunction "1_1") (pintype "passive"))
      (node (ref "C26") (pin "1") (pinfunction "1_1") (pintype "passive"))
      (node (ref "C30") (pin "1") (pinfunction "1_1") (pintype "passive"))
      (node (ref "C31") (pin "1") (pinfunction "1_1") (pintype "passive"))
      (node (ref "C32") (pin "1") (pinfunction "1_1") (pintype "passive"))
      (node (ref "C33") (pin "1") (pinfunction "1_1") (pintype "passive"))
      (node (ref "R12") (pin "2") (pinfunction "2_2") (pintype "passive"))
      (node (ref "R13") (pin "2") (pinfunction "2_2") (pintype "passive"))
      (node (ref "R9") (pin "2") (pinfunction "2_2") (pintype "passive"))
      (node (ref "U$1") (pin "P$3") (pinfunction "VCC_P$3") (pintype "power_in"))
      (node (ref "U$2") (pin "P$3") (pinfunction "VCC_P$3") (pintype "power_in"))
      (node (ref "U4") (pin "P12") (pinfunction "VISO_P12") (pintype "bidirectional"))
      (node (ref "U4") (pin "P17") (pinfunction "VDDISO_P17") (pintype "bidirectional"))
    )
    (net (code "48") (name "VOUT") (class "Default")
      (node (ref "C1") (pin "1") (pinfunction "1_1") (pintype "passive"))
      (node (ref "C2") (pin "1") (pinfunction "1_1") (pintype "passive"))
      (node (ref "C3") (pin "1") (pinfunction "1_1") (pintype "passive"))
      (node (ref "U1") (pin "23") (pinfunction "DVDD_23") (pintype "power_in"))
      (node (ref "U1") (pin "45") (pinfunction "VREG_VOUT_45") (pintype "output"))
      (node (ref "U1") (pin "50") (pinfunction "DVDD_50") (pintype "power_in"))
    )
    (net (code "49") (name "V_USB") (class "Default")
      (node (ref "C13") (pin "1") (pinfunction "1_1") (pintype "passive"))
      (node (ref "C14") (pin "2") (pinfunction "2_2") (pintype "passive"))
      (node (ref "C23") (pin "1") (pinfunction "1_1") (pintype "passive"))
      (node (ref "C25") (pin "1") (pinfunction "1_1") (pintype "passive"))
      (node (ref "L1") (pin "2") (pinfunction "2_2") (pintype "passive"))
      (node (ref "U3") (pin "1") (pinfunction "VIN_1") (pintype "input"))
      (node (ref "U3") (pin "3") (pinfunction "EN_3") (pintype "input"))
      (node (ref "U4") (pin "P9") (pinfunction "VIN_P9") (pintype "bidirectional"))
    )
    (net (code "50") (name "XIN") (class "Default")
      (node (ref "C21") (pin "2") (pinfunction "2_2") (pintype "passive"))
      (node (ref "Q1") (pin "1") (pinfunction "X1_1") (pintype "bidirectional"))
      (node (ref "U1") (pin "20") (pinfunction "XIN_20") (pintype "input"))
    )
    (net (code "51") (name "unconnected-(J1-SBU1-PadA8)") (class "Default")
      (node (ref "J1") (pin "A8") (pinfunction "SBU1_A8") (pintype "bidirectional"))
    )
    (net (code "52") (name "unconnected-(J1-SBU2-PadB8)") (class "Default")
      (node (ref "J1") (pin "B8") (pinfunction "SBU2_B8") (pintype "bidirectional"))
    )
    (net (code "53") (name "unconnected-(LED1-DO-Pad1)") (class "Default")
      (node (ref "LED1") (pin "1") (pinfunction "DO_1") (pintype "bidirectional"))
    )
    (net (code "54") (name "unconnected-(U$1-NC-PadP$2)") (class "Default")
      (node (ref "U$1") (pin "P$2") (pinfunction "NC_P$2") (pintype "no_connect"))
    )
    (net (code "55") (name "unconnected-(U$1-NC-PadP$9)") (class "Default")
      (node (ref "U$1") (pin "P$9") (pinfunction "NC_P$9") (pintype "no_connect"))
    )
    (net (code "56") (name "unconnected-(U$1-NC-PadP$10)") (class "Default")
      (node (ref "U$1") (pin "P$10") (pinfunction "NC_P$10") (pintype "no_connect"))
    )
    (net (code "57") (name "unconnected-(U$2-NC-PadP$2)") (class "Default")
      (node (ref "U$2") (pin "P$2") (pinfunction "NC_P$2") (pintype "no_connect"))
    )
    (net (code "58") (name "unconnected-(U$2-NC-PadP$9)") (class "Default")
      (node (ref "U$2") (pin "P$9") (pinfunction "NC_P$9") (pintype "no_connect"))
    )
    (net (code "59") (name "unconnected-(U$2-NC-PadP$10)") (class "Default")
      (node (ref "U$2") (pin "P$10") (pinfunction "NC_P$10") (pintype "no_connect"))
    )
    (net (code "60") (name "unconnected-(U1-GPIO2-Pad4)") (class "Default")
      (node (ref "U1") (pin "4") (pinfunction "GPIO2_4") (pintype "bidirectional"))
    )
    (net (code "61") (name "unconnected-(U1-GPIO3-Pad5)") (class "Default")
      (node (ref "U1") (pin "5") (pinfunction "GPIO3_5") (pintype "bidirectional"))
    )
    (net (code "62") (name "unconnected-(U1-GPIO4-Pad6)") (class "Default")
      (node (ref "U1") (pin "6") (pinfunction "GPIO4_6") (pintype "bidirectional"))
    )
    (net (code "63") (name "unconnected-(U1-GPIO5-Pad7)") (class "Default")
      (node (ref "U1") (pin "7") (pinfunction "GPIO5_7") (pintype "bidirectional"))
    )
    (net (code "64") (name "unconnected-(U1-GPIO6-Pad8)") (class "Default")
      (node (ref "U1") (pin "8") (pinfunction "GPIO6_8") (pintype "bidirectional"))
    )
    (net (code "65") (name "unconnected-(U1-GPIO7-Pad9)") (class "Default")
      (node (ref "U1") (pin "9") (pinfunction "GPIO7_9") (pintype "bidirectional"))
    )
    (net (code "66") (name "unconnected-(U1-GPIO8-Pad11)") (class "Default")
      (node (ref "U1") (pin "11") (pinfunction "GPIO8_11") (pintype "bidirectional"))
    )
    (net (code "67") (name "unconnected-(U1-GPIO17-Pad28)") (class "Default")
      (node (ref "U1") (pin "28") (pinfunction "GPIO17_28") (pintype "bidirectional"))
    )
    (net (code "68") (name "unconnected-(U1-GPIO21-Pad32)") (class "Default")
      (node (ref "U1") (pin "32") (pinfunction "GPIO21_32") (pintype "bidirectional"))
    )
    (net (code "69") (name "unconnected-(U1-GPIO22-Pad34)") (class "Default")
      (node (ref "U1") (pin "34") (pinfunction "GPIO22_34") (pintype "bidirectional"))
    )
    (net (code "70") (name "unconnected-(U1-GPIO23-Pad35)") (class "Default")
      (node (ref "U1") (pin "35") (pinfunction "GPIO23_35") (pintype "bidirectional"))
    )
    (net (code "71") (name "unconnected-(U1-GPIO24-Pad36)") (class "Default")
      (node (ref "U1") (pin "36") (pinfunction "GPIO24_36") (pintype "bidirectional"))
    )
    (net (code "72") (name "unconnected-(U1-GPIO26{slash}ADC0-Pad38)") (class "Default")
      (node (ref "U1") (pin "38") (pinfunction "GPIO26/ADC0_38") (pintype "bidirectional"))
    )
    (net (code "73") (name "unconnected-(U1-GPIO27{slash}ADC1-Pad39)") (class "Default")
      (node (ref "U1") (pin "39") (pinfunction "GPIO27/ADC1_39") (pintype "bidirectional"))
    )
    (net (code "74") (name "unconnected-(U1-GPIO28{slash}ADC2-Pad40)") (class "Default")
      (node (ref "U1") (pin "40") (pinfunction "GPIO28/ADC2_40") (pintype "bidirectional"))
    )
    (net (code "75") (name "unconnected-(U1-GPIO29{slash}ADC3-Pad41)") (class "Default")
      (node (ref "U1") (pin "41") (pinfunction "GPIO29/ADC3_41") (pintype "bidirectional"))
    )
    (net (code "76") (name "~{BOOT}") (class "Default")
      (node (ref "R5") (pin "2") (pinfunction "2_2") (pintype "passive"))
      (node (ref "S1") (pin "1") (pinfunction "1_1") (pintype "passive"))
      (node (ref "S1") (pin "2") (pinfunction "1_2") (pintype "passive"))
    )
    (net (code "77") (name "~{RESET}") (class "Default")
      (node (ref "S2") (pin "1") (pinfunction "1_1") (pintype "passive"))
      (node (ref "S2") (pin "2") (pinfunction "1_2") (pintype "passive"))
      (node (ref "U1") (pin "26") (pinfunction "RUN_26") (pintype "input"))
    )
  )
)
